# wander-v1_1.net
KiCad netlist of a schematic drawn in EAGLE
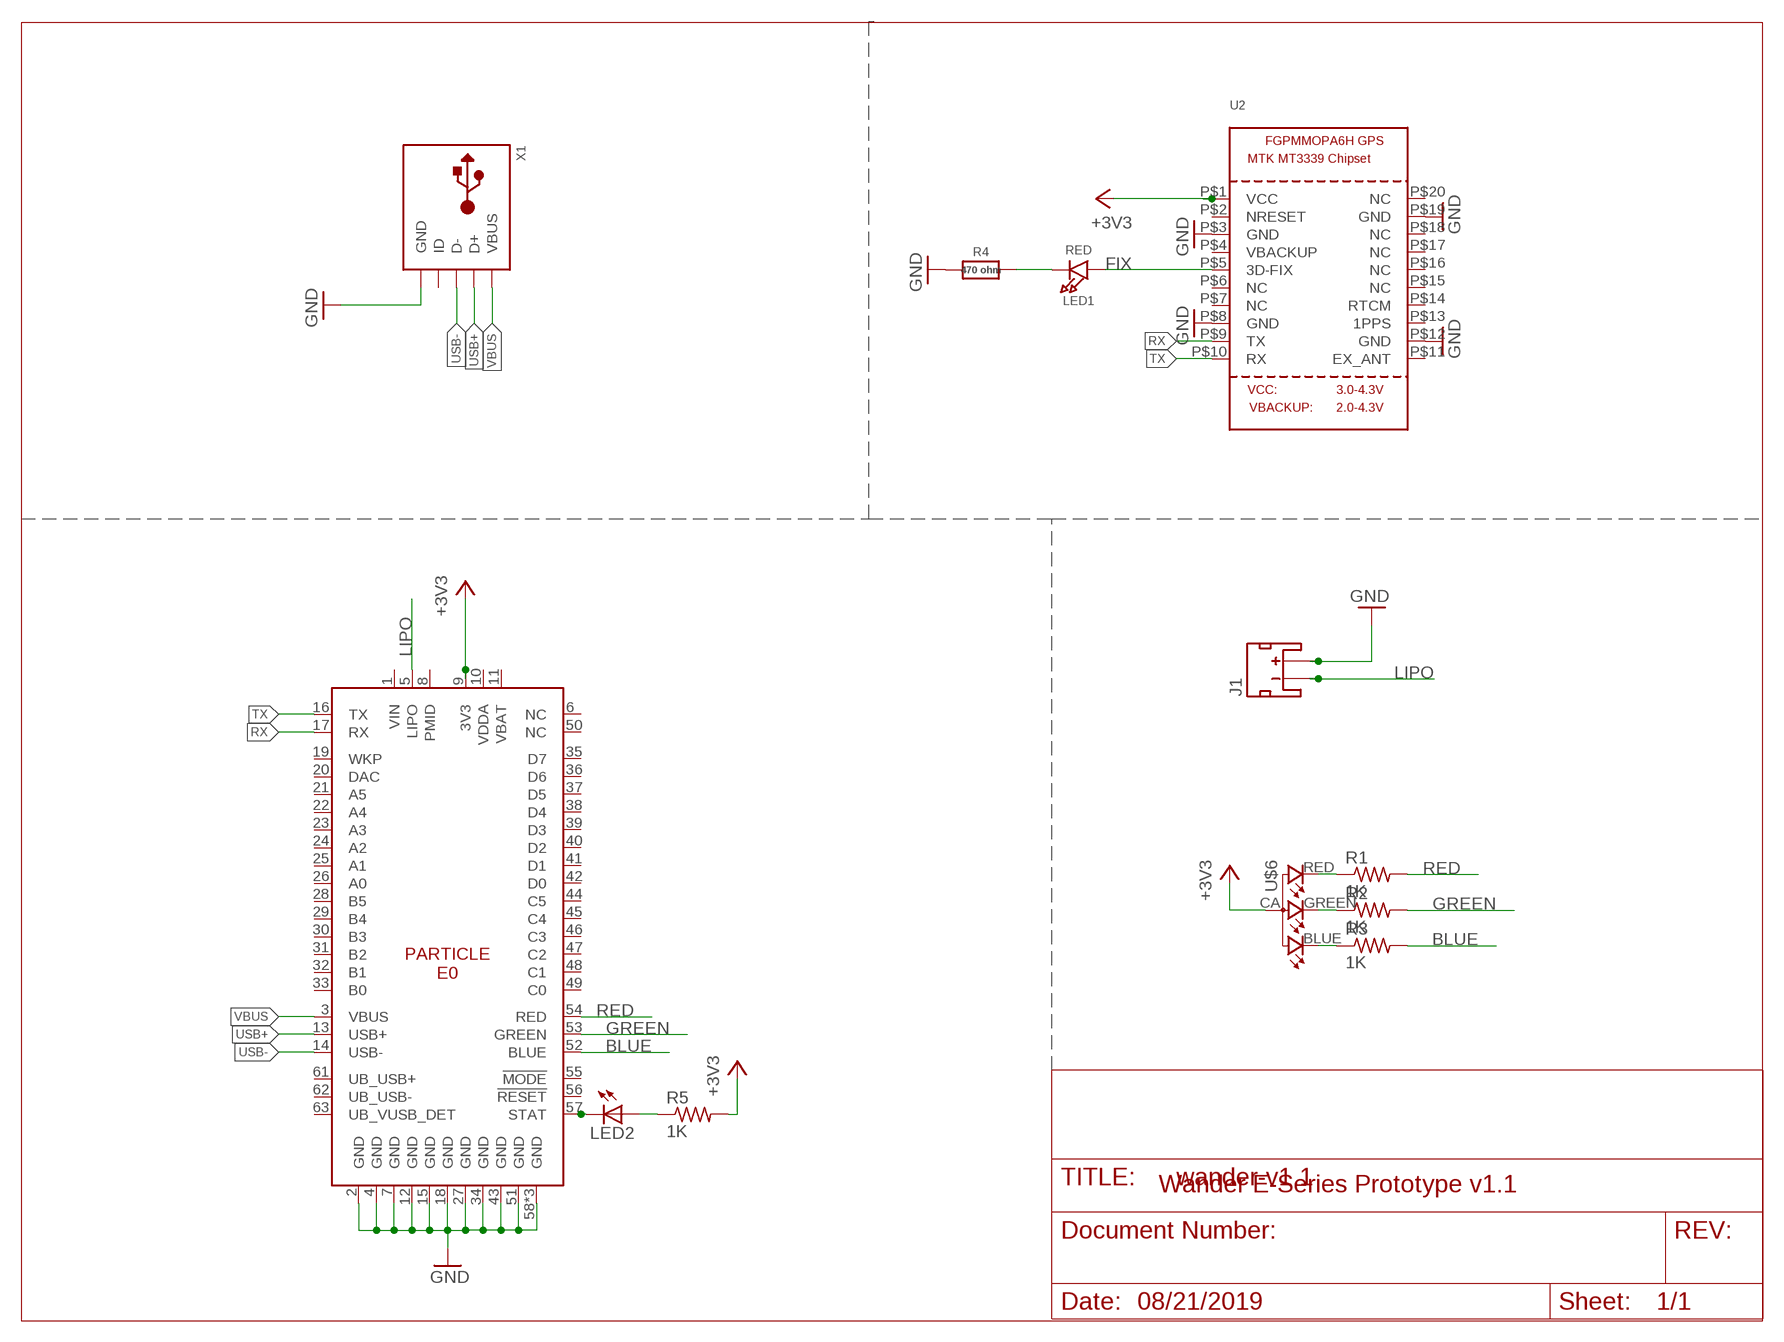
[diagram p0: schematic, sheet 1]

(export (version "E")
  (design (tool "Eeschema 10.0.6"))
  (components
    (comp (ref "J1")
      (value "JST_2MM_MALE")
      (footprint "eagle-import:JST-2-SMD")
      (libsource (lib "eagle-import") (part "JST_2MM_MALE"))
    )
    (comp (ref "LED1")
      (value "RED")
      (footprint "eagle-import:CHIPLED_0805_NOOUTLINE")
      (libsource (lib "eagle-import") (part "LED0805_NOOUTLINE"))
    )
    (comp (ref "LED2")
      (value "LED0603")
      (footprint "eagle-import:LED-0603")
      (libsource (lib "eagle-import") (part "LED0603"))
    )
    (comp (ref "R1")
      (value "1K")
      (footprint "eagle-import:R0603")
      (libsource (lib "eagle-import") (part "R-US_R0603"))
    )
    (comp (ref "R2")
      (value "1K")
      (footprint "eagle-import:R0603")
      (libsource (lib "eagle-import") (part "R-US_R0603"))
    )
    (comp (ref "R3")
      (value "1K")
      (footprint "eagle-import:R0603")
      (libsource (lib "eagle-import") (part "R-US_R0603"))
    )
    (comp (ref "R4")
      (value "470 ohm")
      (footprint "eagle-import:0805-NO")
      (libsource (lib "eagle-import") (part "RESISTOR0805_NOOUTLINE"))
    )
    (comp (ref "R5")
      (value "1K")
      (footprint "eagle-import:R0603")
      (libsource (lib "eagle-import") (part "R-US_R0603"))
    )
    (comp (ref "U$6")
      (value "RGB-LED-CLMVB-FKARGB")
      (footprint "eagle-import:PLCC4-2MM-RGB")
      (libsource (lib "eagle-import") (part "RGB-LED-CLMVB-FKARGB"))
    )
    (comp (ref "U1")
      (value "E0_V005")
      (footprint "eagle-import:E0")
      (libsource (lib "eagle-import") (part "E0_V005"))
    )
    (comp (ref "U2")
      (value "GPS_FGPMMOPA6H")
      (footprint "eagle-import:FGPMMOPA6H")
      (libsource (lib "eagle-import") (part "GPS_FGPMMOPA6H"))
    )
    (comp (ref "X1")
      (value "USB-NEW-PHOTON")
      (footprint "eagle-import:4UCONN_CMCUSB-5BFM14X-01-X")
      (libsource (lib "eagle-import") (part "USB-NEW-PHOTON"))
    )
  )
  (nets
    (net (code "1") (name "+3V3") (class "Default")
      (node (ref "R5") (pin "2") (pinfunction "2_2") (pintype "passive"))
      (node (ref "U$6") (pin "CA") (pinfunction "1_CA") (pintype "passive"))
      (node (ref "U1") (pin "9") (pinfunction "3V3_9") (pintype "bidirectional"))
      (node (ref "U2") (pin "P$1") (pinfunction "VCC_P$1") (pintype "bidirectional"))
    )
    (net (code "2") (name "/BLUE") (class "Default")
      (node (ref "R3") (pin "2") (pinfunction "2_2") (pintype "passive"))
      (node (ref "U1") (pin "52") (pinfunction "BLUE_52") (pintype "bidirectional"))
    )
    (net (code "3") (name "/FIX") (class "Default")
      (node (ref "LED1") (pin "A") (pinfunction "A_A") (pintype "passive"))
      (node (ref "U2") (pin "P$5") (pinfunction "3D-FIX_P$5") (pintype "bidirectional"))
    )
    (net (code "4") (name "/GREEN") (class "Default")
      (node (ref "R2") (pin "2") (pinfunction "2_2") (pintype "passive"))
      (node (ref "U1") (pin "53") (pinfunction "GREEN_53") (pintype "bidirectional"))
    )
    (net (code "5") (name "/LIPO") (class "Default")
      (node (ref "J1") (pin "1") (pinfunction "-_1") (pintype "bidirectional"))
      (node (ref "U1") (pin "5") (pinfunction "LIPO_5") (pintype "bidirectional"))
    )
    (net (code "6") (name "/RED") (class "Default")
      (node (ref "R1") (pin "2") (pinfunction "2_2") (pintype "passive"))
      (node (ref "U1") (pin "54") (pinfunction "RED_54") (pintype "bidirectional"))
    )
    (net (code "7") (name "GND") (class "Default")
      (node (ref "J1") (pin "2") (pinfunction "+_2") (pintype "bidirectional"))
      (node (ref "R4") (pin "1") (pinfunction "1_1") (pintype "passive"))
      (node (ref "U1") (pin "12") (pinfunction "GND_12") (pintype "bidirectional"))
      (node (ref "U1") (pin "15") (pinfunction "GND_15") (pintype "bidirectional"))
      (node (ref "U1") (pin "18") (pinfunction "GND_18") (pintype "bidirectional"))
      (node (ref "U1") (pin "2") (pinfunction "GND_2") (pintype "bidirectional"))
      (node (ref "U1") (pin "27") (pinfunction "GND_27") (pintype "bidirectional"))
      (node (ref "U1") (pin "34") (pinfunction "GND_34") (pintype "bidirectional"))
      (node (ref "U1") (pin "4") (pinfunction "GND_4") (pintype "bidirectional"))
      (node (ref "U1") (pin "43") (pinfunction "GND_43") (pintype "bidirectional"))
      (node (ref "U1") (pin "51") (pinfunction "GND_51") (pintype "bidirectional"))
      (node (ref "U1") (pin "58") (pinfunction "GND_58") (pintype "bidirectional"))
      (node (ref "U1") (pin "59") (pinfunction "GND_59") (pintype "bidirectional"))
      (node (ref "U1") (pin "60") (pinfunction "GND_60") (pintype "bidirectional"))
      (node (ref "U1") (pin "7") (pinfunction "GND_7") (pintype "bidirectional"))
      (node (ref "U2") (pin "P$12") (pinfunction "GND_P$12") (pintype "bidirectional"))
      (node (ref "U2") (pin "P$19") (pinfunction "GND_P$19") (pintype "bidirectional"))
      (node (ref "U2") (pin "P$3") (pinfunction "GND_P$3") (pintype "bidirectional"))
      (node (ref "U2") (pin "P$8") (pinfunction "GND_P$8") (pintype "bidirectional"))
      (node (ref "X1") (pin "P$1") (pinfunction "GND_P$1") (pintype "power_in"))
      (node (ref "X1") (pin "P$10") (pinfunction "GND_P$10") (pintype "power_in"))
      (node (ref "X1") (pin "P$11") (pinfunction "GND_P$11") (pintype "power_in"))
      (node (ref "X1") (pin "P$6") (pinfunction "GND_P$6") (pintype "power_in"))
      (node (ref "X1") (pin "P$7") (pinfunction "GND_P$7") (pintype "power_in"))
      (node (ref "X1") (pin "P$8") (pinfunction "GND_P$8") (pintype "power_in"))
      (node (ref "X1") (pin "P$9") (pinfunction "GND_P$9") (pintype "power_in"))
    )
    (net (code "8") (name "Net-(LED1-PadC)") (class "Default")
      (node (ref "LED1") (pin "C") (pinfunction "C_C") (pintype "passive"))
      (node (ref "R4") (pin "2") (pinfunction "2_2") (pintype "passive"))
    )
    (net (code "9") (name "Net-(LED2-PadA)") (class "Default")
      (node (ref "LED2") (pin "A") (pinfunction "A_A") (pintype "passive"))
      (node (ref "R5") (pin "1") (pinfunction "1_1") (pintype "passive"))
    )
    (net (code "10") (name "Net-(U$6-2)") (class "Default")
      (node (ref "R3") (pin "1") (pinfunction "1_1") (pintype "passive"))
      (node (ref "U$6") (pin "BLUE") (pinfunction "2_BLUE") (pintype "passive"))
    )
    (net (code "11") (name "Net-(U$6-3)") (class "Default")
      (node (ref "R2") (pin "1") (pinfunction "1_1") (pintype "passive"))
      (node (ref "U$6") (pin "GREEN") (pinfunction "3_GREEN") (pintype "passive"))
    )
    (net (code "12") (name "Net-(U$6-4)") (class "Default")
      (node (ref "R1") (pin "1") (pinfunction "1_1") (pintype "passive"))
      (node (ref "U$6") (pin "RED") (pinfunction "4_RED") (pintype "passive"))
    )
    (net (code "13") (name "Net-(U1-STAT)") (class "Default")
      (node (ref "LED2") (pin "C") (pinfunction "C_C") (pintype "passive"))
      (node (ref "U1") (pin "57") (pinfunction "STAT_57") (pintype "bidirectional"))
    )
    (net (code "14") (name "RX") (class "Default")
      (node (ref "U1") (pin "17") (pinfunction "RX_17") (pintype "bidirectional"))
      (node (ref "U2") (pin "P$9") (pinfunction "TX_P$9") (pintype "bidirectional"))
    )
    (net (code "15") (name "TX") (class "Default")
      (node (ref "U1") (pin "16") (pinfunction "TX_16") (pintype "bidirectional"))
      (node (ref "U2") (pin "P$10") (pinfunction "RX_P$10") (pintype "bidirectional"))
    )
    (net (code "16") (name "USB+") (class "Default")
      (node (ref "U1") (pin "13") (pinfunction "USB+_13") (pintype "bidirectional"))
      (node (ref "X1") (pin "P$3") (pinfunction "D+_P$3") (pintype "bidirectional"))
    )
    (net (code "17") (name "USB-") (class "Default")
      (node (ref "U1") (pin "14") (pinfunction "USB-_14") (pintype "bidirectional"))
      (node (ref "X1") (pin "P$4") (pinfunction "D-_P$4") (pintype "bidirectional"))
    )
    (net (code "18") (name "VBUS") (class "Default")
      (node (ref "U1") (pin "3") (pinfunction "VBUS_3") (pintype "bidirectional"))
      (node (ref "X1") (pin "P$5") (pinfunction "VBUS_P$5") (pintype "power_in"))
    )
    (net (code "19") (name "unconnected-(J1-PAD1-PadNC1)") (class "Default")
      (node (ref "J1") (pin "NC1") (pinfunction "PAD1_NC1") (pintype "bidirectional"))
    )
    (net (code "20") (name "unconnected-(J1-PAD2-PadNC2)") (class "Default")
      (node (ref "J1") (pin "NC2") (pinfunction "PAD2_NC2") (pintype "bidirectional"))
    )
    (net (code "21") (name "unconnected-(U1-A0-Pad26)") (class "Default")
      (node (ref "U1") (pin "26") (pinfunction "A0_26") (pintype "bidirectional"))
    )
    (net (code "22") (name "unconnected-(U1-A1-Pad25)") (class "Default")
      (node (ref "U1") (pin "25") (pinfunction "A1_25") (pintype "bidirectional"))
    )
    (net (code "23") (name "unconnected-(U1-A2-Pad24)") (class "Default")
      (node (ref "U1") (pin "24") (pinfunction "A2_24") (pintype "bidirectional"))
    )
    (net (code "24") (name "unconnected-(U1-A3-Pad23)") (class "Default")
      (node (ref "U1") (pin "23") (pinfunction "A3_23") (pintype "bidirectional"))
    )
    (net (code "25") (name "unconnected-(U1-A4-Pad22)") (class "Default")
      (node (ref "U1") (pin "22") (pinfunction "A4_22") (pintype "bidirectional"))
    )
    (net (code "26") (name "unconnected-(U1-A5-Pad21)") (class "Default")
      (node (ref "U1") (pin "21") (pinfunction "A5_21") (pintype "bidirectional"))
    )
    (net (code "27") (name "unconnected-(U1-B0-Pad33)") (class "Default")
      (node (ref "U1") (pin "33") (pinfunction "B0_33") (pintype "bidirectional"))
    )
    (net (code "28") (name "unconnected-(U1-B1-Pad32)") (class "Default")
      (node (ref "U1") (pin "32") (pinfunction "B1_32") (pintype "bidirectional"))
    )
    (net (code "29") (name "unconnected-(U1-B2-Pad31)") (class "Default")
      (node (ref "U1") (pin "31") (pinfunction "B2_31") (pintype "bidirectional"))
    )
    (net (code "30") (name "unconnected-(U1-B3-Pad30)") (class "Default")
      (node (ref "U1") (pin "30") (pinfunction "B3_30") (pintype "bidirectional"))
    )
    (net (code "31") (name "unconnected-(U1-B4-Pad29)") (class "Default")
      (node (ref "U1") (pin "29") (pinfunction "B4_29") (pintype "bidirectional"))
    )
    (net (code "32") (name "unconnected-(U1-B5-Pad28)") (class "Default")
      (node (ref "U1") (pin "28") (pinfunction "B5_28") (pintype "bidirectional"))
    )
    (net (code "33") (name "unconnected-(U1-C0-Pad49)") (class "Default")
      (node (ref "U1") (pin "49") (pinfunction "C0_49") (pintype "bidirectional"))
    )
    (net (code "34") (name "unconnected-(U1-C1-Pad48)") (class "Default")
      (node (ref "U1") (pin "48") (pinfunction "C1_48") (pintype "bidirectional"))
    )
    (net (code "35") (name "unconnected-(U1-C2-Pad47)") (class "Default")
      (node (ref "U1") (pin "47") (pinfunction "C2_47") (pintype "bidirectional"))
    )
    (net (code "36") (name "unconnected-(U1-C3-Pad46)") (class "Default")
      (node (ref "U1") (pin "46") (pinfunction "C3_46") (pintype "bidirectional"))
    )
    (net (code "37") (name "unconnected-(U1-C4-Pad45)") (class "Default")
      (node (ref "U1") (pin "45") (pinfunction "C4_45") (pintype "bidirectional"))
    )
    (net (code "38") (name "unconnected-(U1-C5-Pad44)") (class "Default")
      (node (ref "U1") (pin "44") (pinfunction "C5_44") (pintype "bidirectional"))
    )
    (net (code "39") (name "unconnected-(U1-D0-Pad42)") (class "Default")
      (node (ref "U1") (pin "42") (pinfunction "D0_42") (pintype "bidirectional"))
    )
    (net (code "40") (name "unconnected-(U1-D1-Pad41)") (class "Default")
      (node (ref "U1") (pin "41") (pinfunction "D1_41") (pintype "bidirectional"))
    )
    (net (code "41") (name "unconnected-(U1-D2-Pad40)") (class "Default")
      (node (ref "U1") (pin "40") (pinfunction "D2_40") (pintype "bidirectional"))
    )
    (net (code "42") (name "unconnected-(U1-D3-Pad39)") (class "Default")
      (node (ref "U1") (pin "39") (pinfunction "D3_39") (pintype "bidirectional"))
    )
    (net (code "43") (name "unconnected-(U1-D4-Pad38)") (class "Default")
      (node (ref "U1") (pin "38") (pinfunction "D4_38") (pintype "bidirectional"))
    )
    (net (code "44") (name "unconnected-(U1-D5-Pad37)") (class "Default")
      (node (ref "U1") (pin "37") (pinfunction "D5_37") (pintype "bidirectional"))
    )
    (net (code "45") (name "unconnected-(U1-D6-Pad36)") (class "Default")
      (node (ref "U1") (pin "36") (pinfunction "D6_36") (pintype "bidirectional"))
    )
    (net (code "46") (name "unconnected-(U1-D7-Pad35)") (class "Default")
      (node (ref "U1") (pin "35") (pinfunction "D7_35") (pintype "bidirectional"))
    )
    (net (code "47") (name "unconnected-(U1-DAC-Pad20)") (class "Default")
      (node (ref "U1") (pin "20") (pinfunction "DAC_20") (pintype "bidirectional"))
    )
    (net (code "48") (name "unconnected-(U1-NC-Pad6)") (class "Default")
      (node (ref "U1") (pin "6") (pinfunction "NC_6") (pintype "bidirectional"))
    )
    (net (code "49") (name "unconnected-(U1-NC-Pad50)") (class "Default")
      (node (ref "U1") (pin "50") (pinfunction "NC_50") (pintype "bidirectional"))
    )
    (net (code "50") (name "unconnected-(U1-PMID-Pad8)") (class "Default")
      (node (ref "U1") (pin "8") (pinfunction "PMID_8") (pintype "bidirectional"))
    )
    (net (code "51") (name "unconnected-(U1-UB_USB+-Pad61)") (class "Default")
      (node (ref "U1") (pin "61") (pinfunction "UB_USB+_61") (pintype "bidirectional"))
    )
    (net (code "52") (name "unconnected-(U1-UB_USB--Pad62)") (class "Default")
      (node (ref "U1") (pin "62") (pinfunction "UB_USB-_62") (pintype "bidirectional"))
    )
    (net (code "53") (name "unconnected-(U1-UB_VUSB_DET-Pad63)") (class "Default")
      (node (ref "U1") (pin "63") (pinfunction "UB_VUSB_DET_63") (pintype "bidirectional"))
    )
    (net (code "54") (name "unconnected-(U1-VBAT-Pad11)") (class "Default")
      (node (ref "U1") (pin "11") (pinfunction "VBAT_11") (pintype "bidirectional"))
    )
    (net (code "55") (name "unconnected-(U1-VDDA-Pad10)") (class "Default")
      (node (ref "U1") (pin "10") (pinfunction "VDDA_10") (pintype "bidirectional"))
    )
    (net (code "56") (name "unconnected-(U1-VIN-Pad1)") (class "Default")
      (node (ref "U1") (pin "1") (pinfunction "VIN_1") (pintype "bidirectional"))
    )
    (net (code "57") (name "unconnected-(U1-WKP-Pad19)") (class "Default")
      (node (ref "U1") (pin "19") (pinfunction "WKP_19") (pintype "bidirectional"))
    )
    (net (code "58") (name "unconnected-(U1-~{MODE}-Pad55)") (class "Default")
      (node (ref "U1") (pin "55") (pinfunction "~{MODE}_55") (pintype "bidirectional"))
    )
    (net (code "59") (name "unconnected-(U1-~{RESET}-Pad56)") (class "Default")
      (node (ref "U1") (pin "56") (pinfunction "~{RESET}_56") (pintype "bidirectional"))
    )
    (net (code "60") (name "unconnected-(U2-1PPS-PadP$13)") (class "Default")
      (node (ref "U2") (pin "P$13") (pinfunction "1PPS_P$13") (pintype "bidirectional"))
    )
    (net (code "61") (name "unconnected-(U2-EX_ANT-PadP$11)") (class "Default")
      (node (ref "U2") (pin "P$11") (pinfunction "EX_ANT_P$11") (pintype "bidirectional"))
    )
    (net (code "62") (name "unconnected-(U2-NC-PadP$6)") (class "Default")
      (node (ref "U2") (pin "P$6") (pinfunction "NC_P$6") (pintype "bidirectional"))
    )
    (net (code "63") (name "unconnected-(U2-NC-PadP$7)") (class "Default")
      (node (ref "U2") (pin "P$7") (pinfunction "NC_P$7") (pintype "bidirectional"))
    )
    (net (code "64") (name "unconnected-(U2-NC-PadP$15)") (class "Default")
      (node (ref "U2") (pin "P$15") (pinfunction "NC_P$15") (pintype "bidirectional"))
    )
    (net (code "65") (name "unconnected-(U2-NC-PadP$16)") (class "Default")
      (node (ref "U2") (pin "P$16") (pinfunction "NC_P$16") (pintype "bidirectional"))
    )
    (net (code "66") (name "unconnected-(U2-NC-PadP$17)") (class "Default")
      (node (ref "U2") (pin "P$17") (pinfunction "NC_P$17") (pintype "bidirectional"))
    )
    (net (code "67") (name "unconnected-(U2-NC-PadP$18)") (class "Default")
      (node (ref "U2") (pin "P$18") (pinfunction "NC_P$18") (pintype "bidirectional"))
    )
    (net (code "68") (name "unconnected-(U2-NC-PadP$20)") (class "Default")
      (node (ref "U2") (pin "P$20") (pinfunction "NC_P$20") (pintype "bidirectional"))
    )
    (net (code "69") (name "unconnected-(U2-NRESET-PadP$2)") (class "Default")
      (node (ref "U2") (pin "P$2") (pinfunction "NRESET_P$2") (pintype "bidirectional"))
    )
    (net (code "70") (name "unconnected-(U2-RTCM-PadP$14)") (class "Default")
      (node (ref "U2") (pin "P$14") (pinfunction "RTCM_P$14") (pintype "bidirectional"))
    )
    (net (code "71") (name "unconnected-(U2-VBACKUP-PadP$4)") (class "Default")
      (node (ref "U2") (pin "P$4") (pinfunction "VBACKUP_P$4") (pintype "bidirectional"))
    )
    (net (code "72") (name "unconnected-(X1-ID-PadP$2)") (class "Default")
      (node (ref "X1") (pin "P$2") (pinfunction "ID_P$2") (pintype "bidirectional"))
    )
  )
)
